# macro.net
KiCad netlist of a schematic drawn in EasyEDA Pro
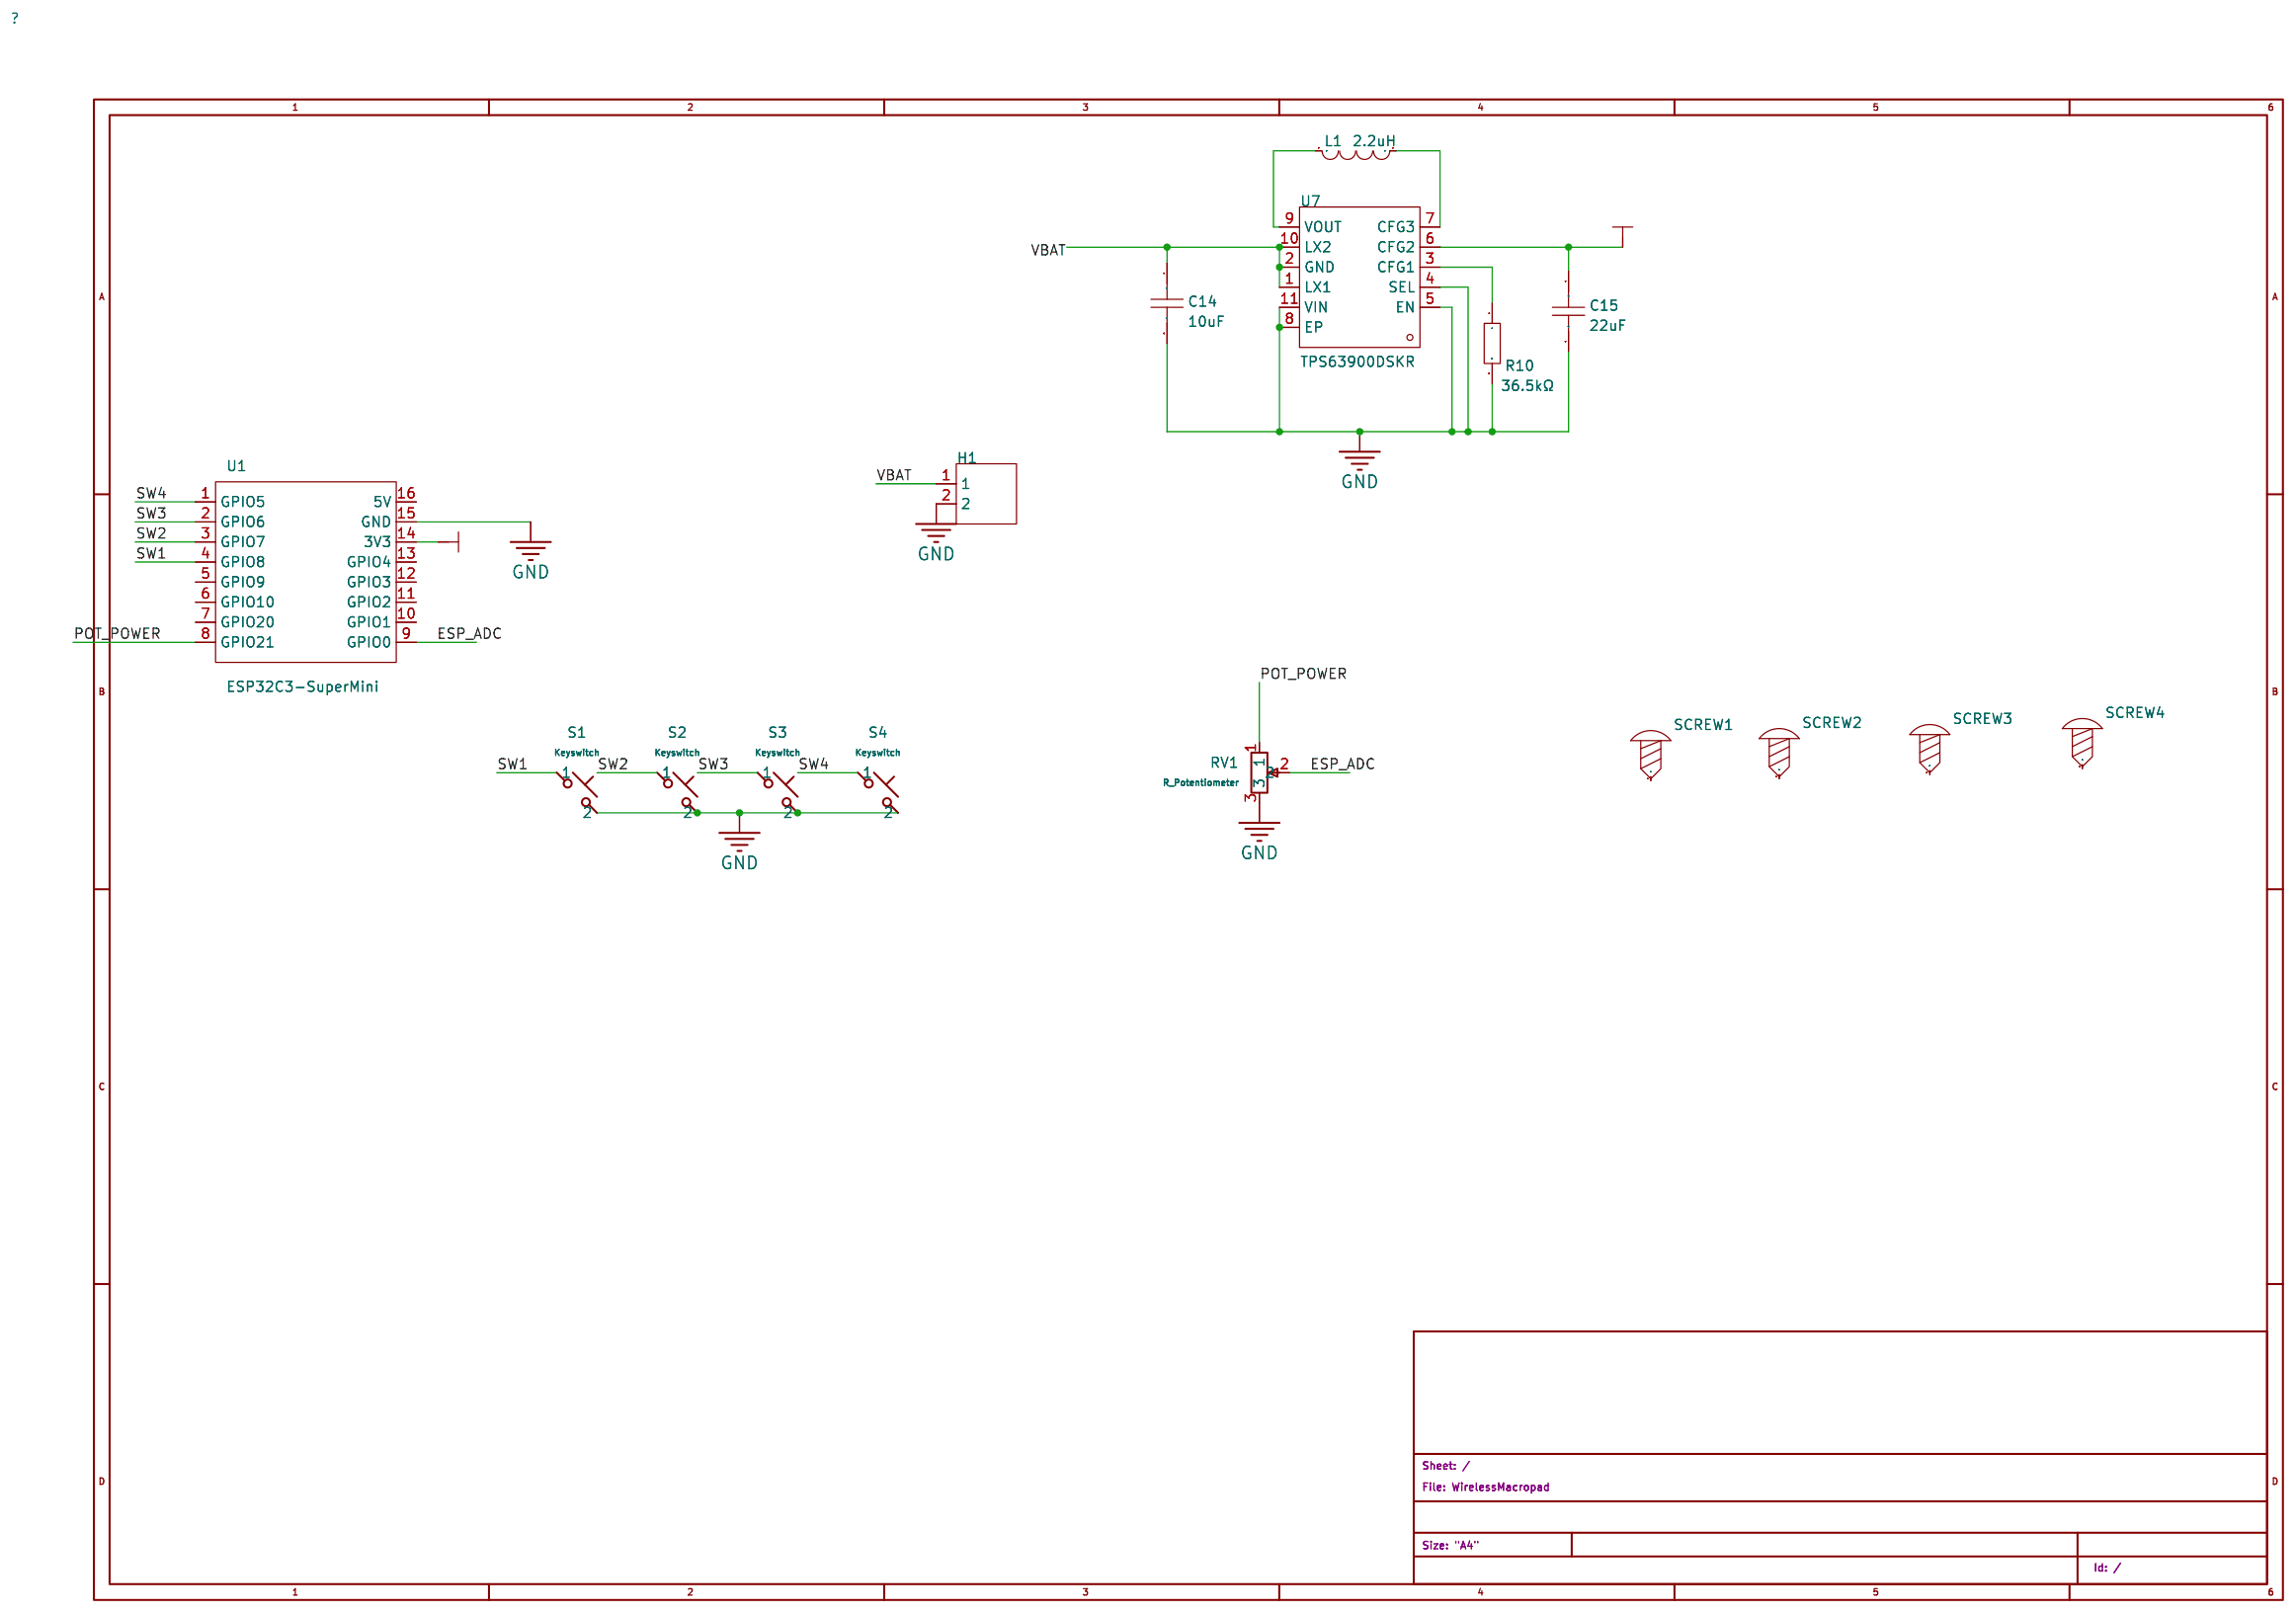
[diagram p0: schematic sheet]

(export (version "E")
  (design (tool "Eeschema 10.0.6"))
  (components
    (comp (ref "C14")
      (value "10uF")
      (fields
        (field (name "Manufacturer Part") "CL05A106MQ5NUNC")
        (field (name "Manufacturer") "SAMSUNG(三星)")
      )
      (libsource (lib "easyedapro") (part "CAP"))
    )
    (comp (ref "C15")
      (value "22uF")
      (fields
        (field (name "Manufacturer Part") "CL21A226MAQNNNE")
        (field (name "Manufacturer") "SAMSUNG(三星)")
      )
      (libsource (lib "easyedapro") (part "CAP"))
    )
    (comp (ref "H1")
      (value "~")
      (footprint "easyedapro:HDR-TH_2P-P2.54-V-M-1")
      (libsource (lib "easyedapro") (part "210S-1*2P L=11.6MMGold-plated black"))
    )
    (comp (ref "L1")
      (value "2.2uH")
      (fields (field (name "Manufacturer Part") "CY43-2.2UH") (field (name "Manufacturer") "SHOU HAN(首韩)"))
      (libsource (lib "easyedapro") (part "电感"))
    )
    (comp (ref "R10")
      (value "36.5kΩ")
      (fields (field (name "Manufacturer Part") "AC0402FR-0736K5L") (field (name "Manufacturer") "YAGEO(国巨)"))
      (libsource (lib "easyedapro") (part "Res"))
    )
    (comp (ref "RV1")
      (value "R_Potentiometer")
      (footprint "easyedapro:ScottoKeebs_Miscellaneous:Sliding_Pot")
      (description "Potentiometer")
      (libsource (lib "easyedapro") (part "Device_R_Potentiometer"))
    )
    (comp (ref "S1")
      (value "Keyswitch")
      (footprint "easyedapro:ScottoKeebs_Hotswap:Hotswap_MX_1.00u")
      (description "Push button switch, normally open, two pins, 45° tilted")
      (libsource (lib "easyedapro") (part "ScottoKeebs_Placeholder_Keyswitch"))
    )
    (comp (ref "S2")
      (value "Keyswitch")
      (footprint "easyedapro:ScottoKeebs_Hotswap:Hotswap_MX_1.00u")
      (description "Push button switch, normally open, two pins, 45° tilted")
      (libsource (lib "easyedapro") (part "ScottoKeebs_Placeholder_Keyswitch"))
    )
    (comp (ref "S3")
      (value "Keyswitch")
      (footprint "easyedapro:ScottoKeebs_Hotswap:Hotswap_MX_1.00u")
      (description "Push button switch, normally open, two pins, 45° tilted")
      (libsource (lib "easyedapro") (part "ScottoKeebs_Placeholder_Keyswitch"))
    )
    (comp (ref "S4")
      (value "Keyswitch")
      (footprint "easyedapro:ScottoKeebs_Hotswap:Hotswap_MX_1.00u")
      (description "Push button switch, normally open, two pins, 45° tilted")
      (libsource (lib "easyedapro") (part "ScottoKeebs_Placeholder_Keyswitch"))
    )
    (comp (ref "SCREW1")
      (value "~")
      (footprint "easyedapro:Screw-Hole-M2")
      (libsource (lib "easyedapro") (part "Screw-Hole"))
    )
    (comp (ref "SCREW2")
      (value "~")
      (footprint "easyedapro:Screw-Hole-M2")
      (libsource (lib "easyedapro") (part "Screw-Hole"))
    )
    (comp (ref "SCREW3")
      (value "~")
      (footprint "easyedapro:Screw-Hole-M2")
      (libsource (lib "easyedapro") (part "Screw-Hole"))
    )
    (comp (ref "SCREW4")
      (value "~")
      (footprint "easyedapro:Screw-Hole-M2")
      (libsource (lib "easyedapro") (part "Screw-Hole"))
    )
    (comp (ref "U1")
      (value "ESP32C3-SuperMini")
      (footprint "easyedapro:COMM-SMD_16P-L22.5-W18.0-P2.54-TL")
      (libsource (lib "easyedapro") (part "ESP32C3-SUPERMINI"))
    )
    (comp (ref "U7")
      (value "TPS63900DSKR")
      (footprint "easyedapro:WSON-10_L2.5-W2.5-W0.50-TL-EP")
      (fields (field (name "Manufacturer") "TI(德州仪器)"))
      (libsource (lib "easyedapro") (part "TPS63900DSKR"))
    )
  )
  (nets
    (net (code "1") (name "+3V3") (class "Default")
      (node (ref "C15") (pin "1") (pinfunction "1_1") (pintype "input"))
      (node (ref "U1") (pin "14") (pinfunction "3V3_14") (pintype "unspecified"))
      (node (ref "U7") (pin "6") (pinfunction "CFG2_6") (pintype "unspecified"))
    )
    (net (code "2") (name "/ESP_ADC") (class "Default")
      (node (ref "RV1") (pin "2") (pinfunction "2_2") (pintype "unspecified"))
      (node (ref "U1") (pin "9") (pinfunction "GPIO0_9") (pintype "unspecified"))
    )
    (net (code "3") (name "/POT_POWER") (class "Default")
      (node (ref "RV1") (pin "1") (pinfunction "1_1") (pintype "unspecified"))
      (node (ref "U1") (pin "8") (pinfunction "GPIO21_8") (pintype "unspecified"))
    )
    (net (code "4") (name "/SW1") (class "Default")
      (node (ref "S1") (pin "1") (pinfunction "1_1") (pintype "unspecified"))
      (node (ref "U1") (pin "4") (pinfunction "GPIO8_4") (pintype "unspecified"))
    )
    (net (code "5") (name "/SW2") (class "Default")
      (node (ref "S2") (pin "1") (pinfunction "1_1") (pintype "unspecified"))
      (node (ref "U1") (pin "3") (pinfunction "GPIO7_3") (pintype "unspecified"))
    )
    (net (code "6") (name "/SW3") (class "Default")
      (node (ref "S3") (pin "1") (pinfunction "1_1") (pintype "unspecified"))
      (node (ref "U1") (pin "2") (pinfunction "GPIO6_2") (pintype "unspecified"))
    )
    (net (code "7") (name "/SW4") (class "Default")
      (node (ref "S4") (pin "1") (pinfunction "1_1") (pintype "unspecified"))
      (node (ref "U1") (pin "1") (pinfunction "GPIO5_1") (pintype "unspecified"))
    )
    (net (code "8") (name "/VBAT") (class "Default")
      (node (ref "C14") (pin "1") (pinfunction "1_1") (pintype "input"))
      (node (ref "H1") (pin "1") (pinfunction "1_1") (pintype "unspecified"))
      (node (ref "U7") (pin "1") (pinfunction "LX1_1") (pintype "unspecified"))
      (node (ref "U7") (pin "10") (pinfunction "LX2_10") (pintype "unspecified"))
      (node (ref "U7") (pin "2") (pinfunction "GND_2") (pintype "unspecified"))
    )
    (net (code "9") (name "GND") (class "Default")
      (node (ref "C14") (pin "2") (pinfunction "2_2") (pintype "input"))
      (node (ref "C15") (pin "2") (pinfunction "2_2") (pintype "input"))
      (node (ref "H1") (pin "2") (pinfunction "2_2") (pintype "unspecified"))
      (node (ref "R10") (pin "2") (pinfunction "2_2") (pintype "input"))
      (node (ref "RV1") (pin "3") (pinfunction "3_3") (pintype "unspecified"))
      (node (ref "S1") (pin "2") (pinfunction "2_2") (pintype "unspecified"))
      (node (ref "S2") (pin "2") (pinfunction "2_2") (pintype "unspecified"))
      (node (ref "S3") (pin "2") (pinfunction "2_2") (pintype "unspecified"))
      (node (ref "S4") (pin "2") (pinfunction "2_2") (pintype "unspecified"))
      (node (ref "U1") (pin "15") (pinfunction "GND_15") (pintype "unspecified"))
      (node (ref "U7") (pin "11") (pinfunction "VIN_11") (pintype "unspecified"))
      (node (ref "U7") (pin "4") (pinfunction "SEL_4") (pintype "unspecified"))
      (node (ref "U7") (pin "5") (pinfunction "EN_5") (pintype "unspecified"))
      (node (ref "U7") (pin "8") (pinfunction "EP_8") (pintype "unspecified"))
    )
    (net (code "10") (name "Net-(U7-CFG1)") (class "Default")
      (node (ref "R10") (pin "1") (pinfunction "1_1") (pintype "input"))
      (node (ref "U7") (pin "3") (pinfunction "CFG1_3") (pintype "unspecified"))
    )
    (net (code "11") (name "Net-(U7-CFG3)") (class "Default")
      (node (ref "L1") (pin "1") (pinfunction "1_1") (pintype "input"))
      (node (ref "U7") (pin "7") (pinfunction "CFG3_7") (pintype "unspecified"))
    )
    (net (code "12") (name "Net-(U7-VOUT)") (class "Default")
      (node (ref "L1") (pin "2") (pinfunction "2_2") (pintype "input"))
      (node (ref "U7") (pin "9") (pinfunction "VOUT_9") (pintype "unspecified"))
    )
    (net (code "13") (name "unconnected-(SCREW1-Pad1)") (class "Default")
      (node (ref "SCREW1") (pin "1") (pinfunction "1_1") (pintype "input"))
    )
    (net (code "14") (name "unconnected-(SCREW2-Pad1)") (class "Default")
      (node (ref "SCREW2") (pin "1") (pinfunction "1_1") (pintype "input"))
    )
    (net (code "15") (name "unconnected-(SCREW3-Pad1)") (class "Default")
      (node (ref "SCREW3") (pin "1") (pinfunction "1_1") (pintype "input"))
    )
    (net (code "16") (name "unconnected-(SCREW4-Pad1)") (class "Default")
      (node (ref "SCREW4") (pin "1") (pinfunction "1_1") (pintype "input"))
    )
    (net (code "17") (name "unconnected-(U1-5V-Pad16)") (class "Default")
      (node (ref "U1") (pin "16") (pinfunction "5V_16") (pintype "unspecified"))
    )
    (net (code "18") (name "unconnected-(U1-GPIO1-Pad10)") (class "Default")
      (node (ref "U1") (pin "10") (pinfunction "GPIO1_10") (pintype "unspecified"))
    )
    (net (code "19") (name "unconnected-(U1-GPIO2-Pad11)") (class "Default")
      (node (ref "U1") (pin "11") (pinfunction "GPIO2_11") (pintype "unspecified"))
    )
    (net (code "20") (name "unconnected-(U1-GPIO3-Pad12)") (class "Default")
      (node (ref "U1") (pin "12") (pinfunction "GPIO3_12") (pintype "unspecified"))
    )
    (net (code "21") (name "unconnected-(U1-GPIO4-Pad13)") (class "Default")
      (node (ref "U1") (pin "13") (pinfunction "GPIO4_13") (pintype "unspecified"))
    )
    (net (code "22") (name "unconnected-(U1-GPIO9-Pad5)") (class "Default")
      (node (ref "U1") (pin "5") (pinfunction "GPIO9_5") (pintype "unspecified"))
    )
    (net (code "23") (name "unconnected-(U1-GPIO10-Pad6)") (class "Default")
      (node (ref "U1") (pin "6") (pinfunction "GPIO10_6") (pintype "unspecified"))
    )
    (net (code "24") (name "unconnected-(U1-GPIO20-Pad7)") (class "Default")
      (node (ref "U1") (pin "7") (pinfunction "GPIO20_7") (pintype "unspecified"))
    )
  )
)
